# targetboard3.net
KiCad netlist of a schematic drawn in EAGLE
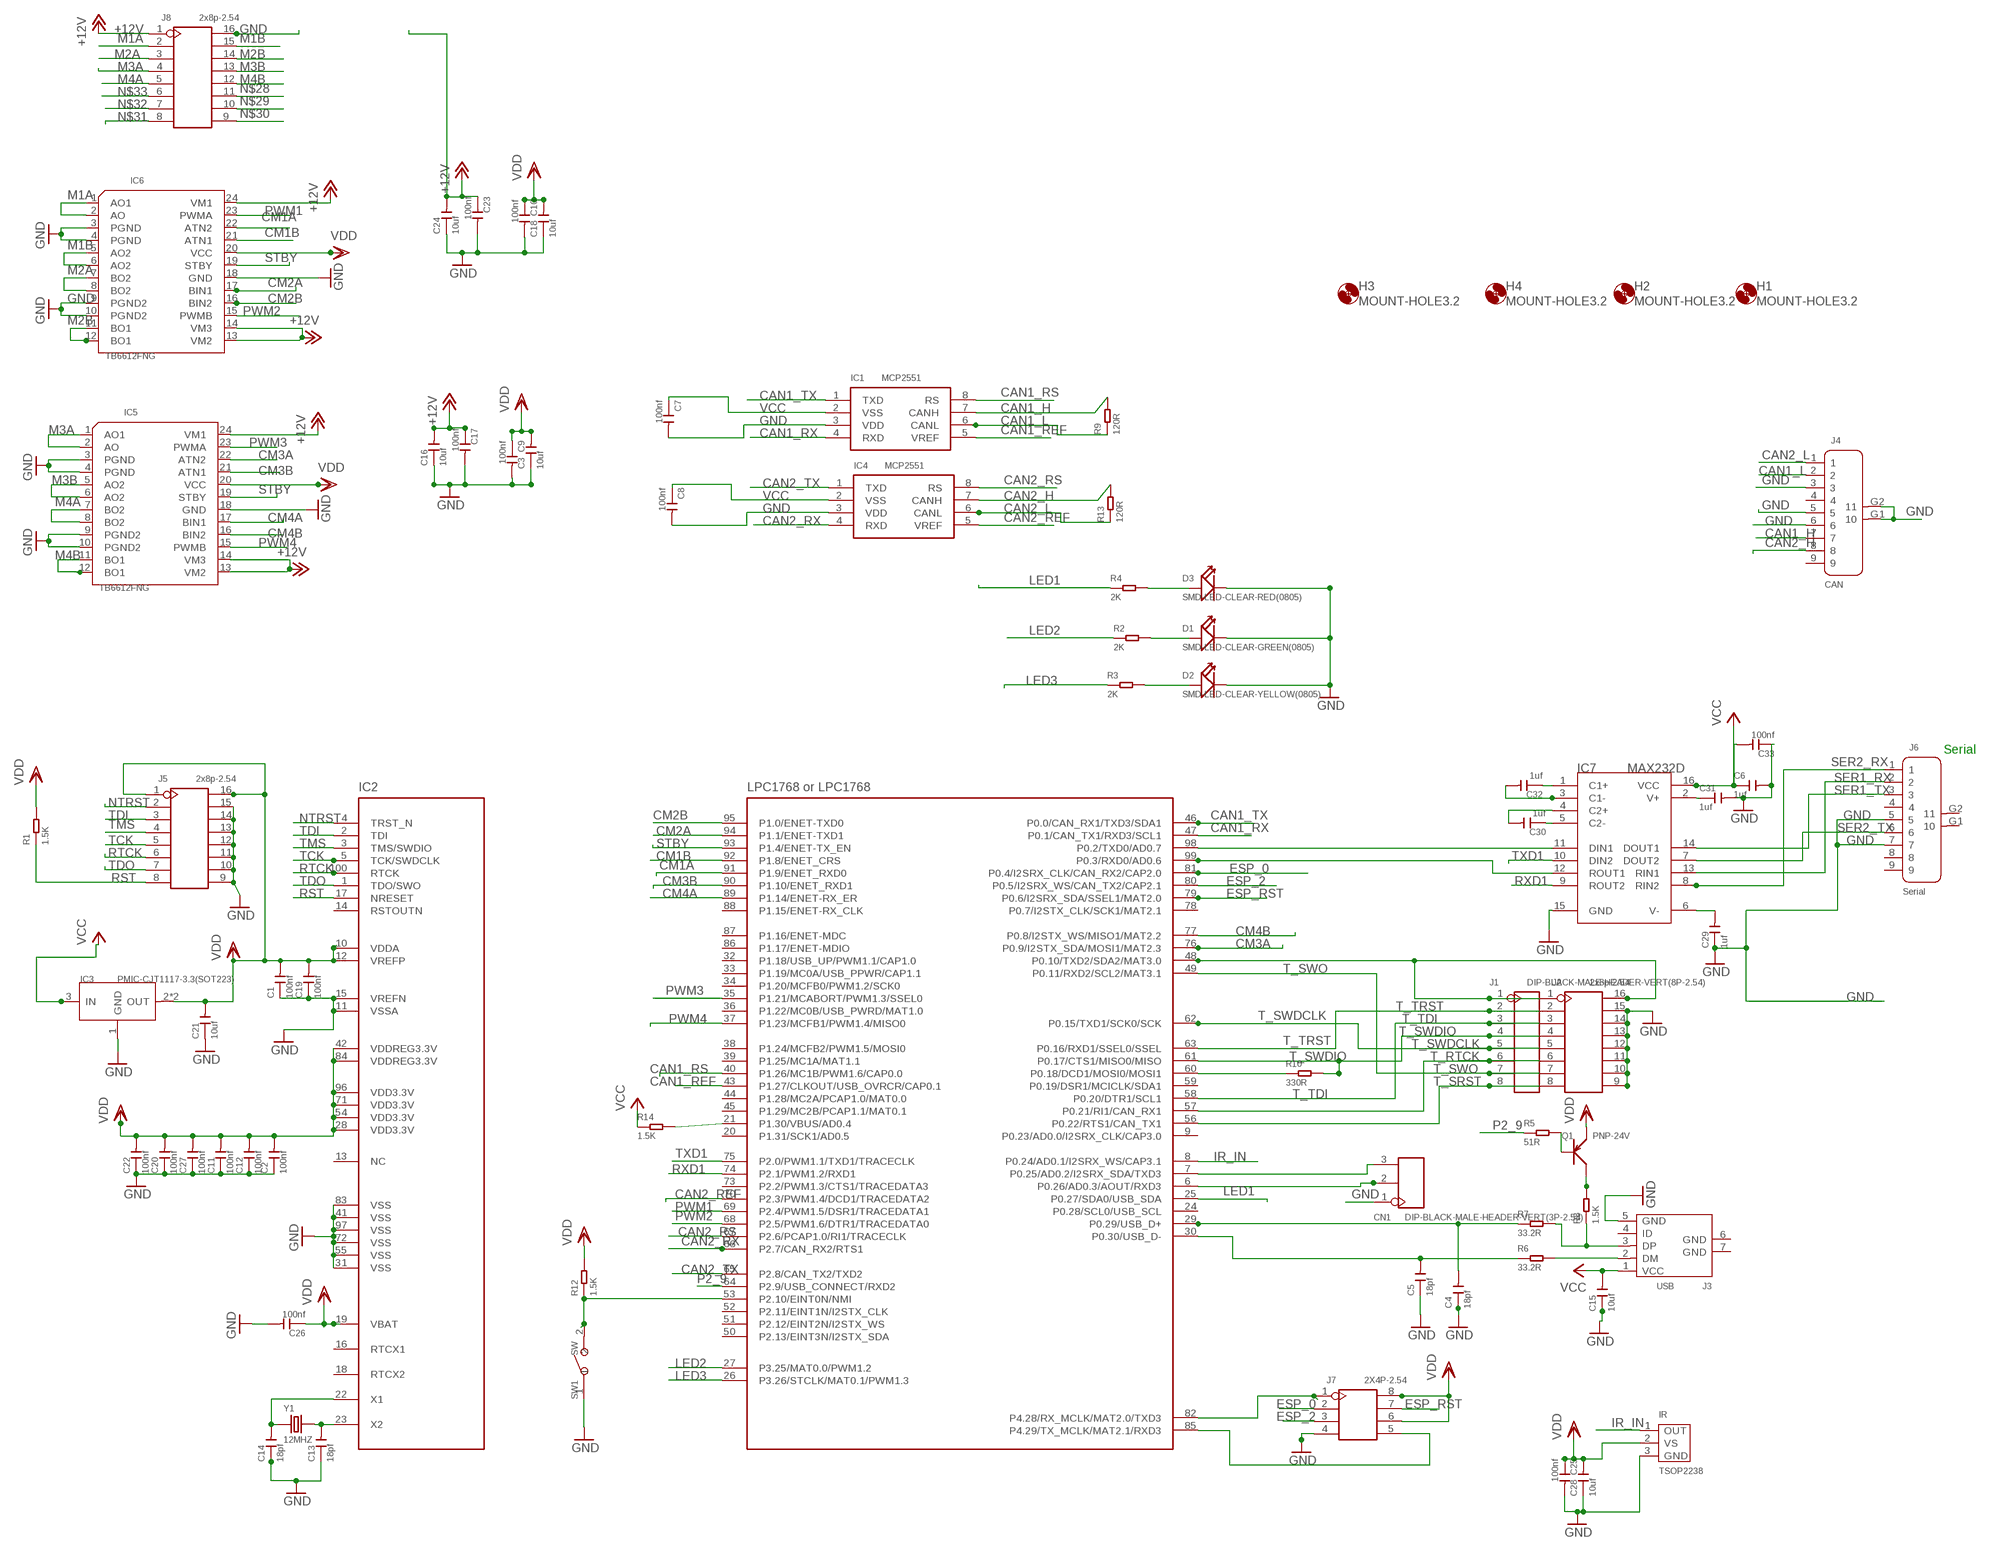
[diagram p0: schematic, sheet 1]

(export (version "E")
  (design (tool "Eeschema 10.0.6"))
  (components
    (comp (ref "C1")
      (value "100nf")
      (footprint "eagle-import:C0805")
      (fields (field (name "MPN") "CC0805KRX7R9BB104"))
      (libsource (lib "eagle-import") (part "CERAMIC-100NF-50V-10%-X7R(0805)"))
    )
    (comp (ref "C2")
      (value "100nf")
      (footprint "eagle-import:C0805")
      (fields (field (name "MPN") "CC0805KRX7R9BB104"))
      (libsource (lib "eagle-import") (part "CERAMIC-100NF-50V-10%-X7R(0805)"))
    )
    (comp (ref "C3")
      (value "10uf")
      (footprint "eagle-import:C0805")
      (fields (field (name "MPN") "CC0805KKX5R8BB106"))
      (libsource (lib "eagle-import") (part "CERAMIC-10UF-25V-10%-X5R(0805)"))
    )
    (comp (ref "C4")
      (value "18pf")
      (footprint "eagle-import:C0805")
      (libsource (lib "eagle-import") (part "CERAMIC-18PF-50V-5%-NPO(0805)"))
    )
    (comp (ref "C5")
      (value "18pf")
      (footprint "eagle-import:C0805")
      (libsource (lib "eagle-import") (part "CERAMIC-18PF-50V-5%-NPO(0805)"))
    )
    (comp (ref "C6")
      (value "1uf")
      (footprint "eagle-import:C0805")
      (fields (field (name "MPN") "CC0805KKX7R8BB105"))
      (libsource (lib "eagle-import") (part "CERAMIC-1UF-25V-10%-X7R(0805)"))
    )
    (comp (ref "C7")
      (value "100nf")
      (footprint "eagle-import:C0805")
      (fields (field (name "MPN") "CC0805KRX7R9BB104"))
      (libsource (lib "eagle-import") (part "CERAMIC-100NF-50V-10%-X7R(0805)"))
    )
    (comp (ref "C8")
      (value "100nf")
      (footprint "eagle-import:C0805")
      (fields (field (name "MPN") "CC0805KRX7R9BB104"))
      (libsource (lib "eagle-import") (part "CERAMIC-100NF-50V-10%-X7R(0805)"))
    )
    (comp (ref "C9")
      (value "100nf")
      (footprint "eagle-import:C0805")
      (fields (field (name "MPN") "CC0805KRX7R9BB104"))
      (libsource (lib "eagle-import") (part "CERAMIC-100NF-50V-10%-X7R(0805)"))
    )
    (comp (ref "C10")
      (value "100nf")
      (footprint "eagle-import:C0805")
      (fields (field (name "MPN") "CC0805KRX7R9BB104"))
      (libsource (lib "eagle-import") (part "CERAMIC-100NF-50V-10%-X7R(0805)"))
    )
    (comp (ref "C11")
      (value "100nf")
      (footprint "eagle-import:C0805")
      (fields (field (name "MPN") "CC0805KRX7R9BB104"))
      (libsource (lib "eagle-import") (part "CERAMIC-100NF-50V-10%-X7R(0805)"))
    )
    (comp (ref "C12")
      (value "100nf")
      (footprint "eagle-import:C0805")
      (fields (field (name "MPN") "CC0805KRX7R9BB104"))
      (libsource (lib "eagle-import") (part "CERAMIC-100NF-50V-10%-X7R(0805)"))
    )
    (comp (ref "C13")
      (value "18pf")
      (footprint "eagle-import:C0805")
      (libsource (lib "eagle-import") (part "CERAMIC-18PF-50V-5%-NPO(0805)"))
    )
    (comp (ref "C14")
      (value "18pf")
      (footprint "eagle-import:C0805")
      (libsource (lib "eagle-import") (part "CERAMIC-18PF-50V-5%-NPO(0805)"))
    )
    (comp (ref "C15")
      (value "10uf")
      (footprint "eagle-import:C0603")
      (fields (field (name "MPN") "CC0603KRX5R6BB106"))
      (libsource (lib "eagle-import") (part "CERAMIC-10UF-10V-10%-X5R(0603)"))
    )
    (comp (ref "C16")
      (value "10uf")
      (footprint "eagle-import:C0805")
      (fields (field (name "MPN") "CC0805KKX5R8BB106"))
      (libsource (lib "eagle-import") (part "CERAMIC-10UF-25V-10%-X5R(0805)"))
    )
    (comp (ref "C17")
      (value "100nf")
      (footprint "eagle-import:C0805")
      (fields (field (name "MPN") "CC0805KRX7R9BB104"))
      (libsource (lib "eagle-import") (part "CERAMIC-100NF-50V-10%-X7R(0805)"))
    )
    (comp (ref "C18")
      (value "10uf")
      (footprint "eagle-import:C0805")
      (fields (field (name "MPN") "CC0805KKX5R8BB106"))
      (libsource (lib "eagle-import") (part "CERAMIC-10UF-25V-10%-X5R(0805)"))
    )
    (comp (ref "C19")
      (value "100nf")
      (footprint "eagle-import:C0805")
      (fields (field (name "MPN") "CC0805KRX7R9BB104"))
      (libsource (lib "eagle-import") (part "CERAMIC-100NF-50V-10%-X7R(0805)"))
    )
    (comp (ref "C20")
      (value "100nf")
      (footprint "eagle-import:C0805")
      (fields (field (name "MPN") "CC0805KRX7R9BB104"))
      (libsource (lib "eagle-import") (part "CERAMIC-100NF-50V-10%-X7R(0805)"))
    )
    (comp (ref "C21")
      (value "10uf")
      (footprint "eagle-import:C0805")
      (fields (field (name "MPN") "CC0805KKX5R8BB106"))
      (libsource (lib "eagle-import") (part "CERAMIC-10UF-25V-10%-X5R(0805)"))
    )
    (comp (ref "C22")
      (value "100nf")
      (footprint "eagle-import:C0805")
      (fields (field (name "MPN") "CC0805KRX7R9BB104"))
      (libsource (lib "eagle-import") (part "CERAMIC-100NF-50V-10%-X7R(0805)"))
    )
    (comp (ref "C23")
      (value "100nf")
      (footprint "eagle-import:C0805")
      (fields (field (name "MPN") "CC0805KRX7R9BB104"))
      (libsource (lib "eagle-import") (part "CERAMIC-100NF-50V-10%-X7R(0805)"))
    )
    (comp (ref "C24")
      (value "10uf")
      (footprint "eagle-import:C0805")
      (fields (field (name "MPN") "CC0805KKX5R8BB106"))
      (libsource (lib "eagle-import") (part "CERAMIC-10UF-25V-10%-X5R(0805)"))
    )
    (comp (ref "C25")
      (value "100nf")
      (footprint "eagle-import:C0805")
      (fields (field (name "MPN") "CC0805KRX7R9BB104"))
      (libsource (lib "eagle-import") (part "CERAMIC-100NF-50V-10%-X7R(0805)"))
    )
    (comp (ref "C26")
      (value "100nf")
      (footprint "eagle-import:C0805")
      (fields (field (name "MPN") "CC0805KRX7R9BB104"))
      (libsource (lib "eagle-import") (part "CERAMIC-100NF-50V-10%-X7R(0805)"))
    )
    (comp (ref "C27")
      (value "100nf")
      (footprint "eagle-import:C0805")
      (fields (field (name "MPN") "CC0805KRX7R9BB104"))
      (libsource (lib "eagle-import") (part "CERAMIC-100NF-50V-10%-X7R(0805)"))
    )
    (comp (ref "C28")
      (value "10uf")
      (footprint "eagle-import:C0805")
      (fields (field (name "MPN") "CC0805KKX5R8BB106"))
      (libsource (lib "eagle-import") (part "CERAMIC-10UF-25V-10%-X5R(0805)"))
    )
    (comp (ref "C29")
      (value "1uf")
      (footprint "eagle-import:C0805")
      (fields (field (name "MPN") "CC0805KKX7R8BB105"))
      (libsource (lib "eagle-import") (part "CERAMIC-1UF-25V-10%-X7R(0805)"))
    )
    (comp (ref "C30")
      (value "1uf")
      (footprint "eagle-import:C0805")
      (fields (field (name "MPN") "CC0805KKX7R8BB105"))
      (libsource (lib "eagle-import") (part "CERAMIC-1UF-25V-10%-X7R(0805)"))
    )
    (comp (ref "C31")
      (value "1uf")
      (footprint "eagle-import:C0805")
      (fields (field (name "MPN") "CC0805KKX7R8BB105"))
      (libsource (lib "eagle-import") (part "CERAMIC-1UF-25V-10%-X7R(0805)"))
    )
    (comp (ref "C32")
      (value "1uf")
      (footprint "eagle-import:C0805")
      (fields (field (name "MPN") "CC0805KKX7R8BB105"))
      (libsource (lib "eagle-import") (part "CERAMIC-1UF-25V-10%-X7R(0805)"))
    )
    (comp (ref "C33")
      (value "100nf")
      (footprint "eagle-import:C0805")
      (fields (field (name "MPN") "CC0805KRX7R9BB104"))
      (libsource (lib "eagle-import") (part "CERAMIC-100NF-50V-10%-X7R(0805)"))
    )
    (comp (ref "CN1")
      (value "DIP-BLACK-MALE-HEADER-VERT(3P-2.54)")
      (footprint "eagle-import:H3-2.54")
      (libsource (lib "eagle-import") (part "DIP-BLACK-MALE-HEADER-VERT(3P-2.54)"))
    )
    (comp (ref "D1")
      (value "SMD-LED-CLEAR-GREEN(0805)")
      (footprint "eagle-import:LED-0805")
      (fields (field (name "MPN") "17-215SYGC/S530-E2/TR8"))
      (libsource (lib "eagle-import") (part "SMD-LED-CLEAR-GREEN(0805)"))
    )
    (comp (ref "D2")
      (value "SMD-LED-CLEAR-YELLOW(0805)")
      (footprint "eagle-import:LED-0805")
      (fields (field (name "MPN") "17-215UYC/S530-A3/TR8"))
      (libsource (lib "eagle-import") (part "SMD-LED-CLEAR-YELLOW(0805)"))
    )
    (comp (ref "D3")
      (value "SMD-LED-CLEAR-RED(0805)")
      (footprint "eagle-import:LED-0805")
      (fields (field (name "MPN") "17-215SURC/S530-A2/TR8"))
      (libsource (lib "eagle-import") (part "SMD-LED-CLEAR-RED(0805)"))
    )
    (comp (ref "H1")
      (value "MOUNT-HOLE3.2")
      (footprint "eagle-import:3,2")
      (libsource (lib "eagle-import") (part "MOUNT-HOLE3.2"))
    )
    (comp (ref "H2")
      (value "MOUNT-HOLE3.2")
      (footprint "eagle-import:3,2")
      (libsource (lib "eagle-import") (part "MOUNT-HOLE3.2"))
    )
    (comp (ref "H3")
      (value "MOUNT-HOLE3.2")
      (footprint "eagle-import:3,2")
      (libsource (lib "eagle-import") (part "MOUNT-HOLE3.2"))
    )
    (comp (ref "H4")
      (value "MOUNT-HOLE3.2")
      (footprint "eagle-import:3,2")
      (libsource (lib "eagle-import") (part "MOUNT-HOLE3.2"))
    )
    (comp (ref "IC1")
      (value "MCP2551")
      (footprint "eagle-import:SOIC8-1.27-5X4MM")
      (fields (field (name "MPN") "MCP2551-I/SN"))
      (libsource (lib "eagle-import") (part "INTERFACE-MCP2551-I/SN(SOIC8)"))
    )
    (comp (ref "IC2")
      (value "LPC1768 or LPC1768")
      (footprint "eagle-import:LQFP100-0.5-13.8X13.8MM")
      (fields (field (name "MPN") "LPC1768FBD100"))
      (libsource (lib "eagle-import") (part "MCU_LPC1768FBD100(LQFP100)"))
    )
    (comp (ref "IC3")
      (value "PMIC-CJT1117-3.3(SOT223)")
      (footprint "eagle-import:SOT-223")
      (fields (field (name "MPN") "CJT1117-3.3"))
      (libsource (lib "eagle-import") (part "PMIC-CJT1117-3.3(SOT223)"))
    )
    (comp (ref "IC4")
      (value "MCP2551")
      (footprint "eagle-import:SOIC8-1.27-5X4MM")
      (fields (field (name "MPN") "MCP2551-I/SN"))
      (libsource (lib "eagle-import") (part "INTERFACE-MCP2551-I/SN(SOIC8)"))
    )
    (comp (ref "IC5")
      (value "TB6612FNG")
      (footprint "eagle-import:SSOP24-0.65-8.9X5.3MM")
      (fields (field (name "MPN") "TB6612FNG-O/C8/EL"))
      (libsource (lib "eagle-import") (part "DRIVER-TB6612FNG-O/C8/EL(SSOP24)"))
    )
    (comp (ref "IC6")
      (value "TB6612FNG")
      (footprint "eagle-import:SSOP24-0.65-8.9X5.3MM")
      (fields (field (name "MPN") "TB6612FNG-O/C8/EL"))
      (libsource (lib "eagle-import") (part "DRIVER-TB6612FNG-O/C8/EL(SSOP24)"))
    )
    (comp (ref "IC7")
      (value "MAX232D")
      (footprint "eagle-import:SOIC16-1.27-10X3.9MM")
      (libsource (lib "eagle-import") (part "RECEIVER-MAX232D(SOIC16)"))
    )
    (comp (ref "IR")
      (value "TSOP2238")
      (footprint "eagle-import:SNR3-2.54-6.95X6.0X5.6MM")
      (libsource (lib "eagle-import") (part "OPTICAL-TSOP2238"))
    )
    (comp (ref "J1")
      (value "DIP-BLACK-MALE-HEADER-VERT(8P-2.54)")
      (footprint "eagle-import:H8-2.54")
      (fields (field (name "MPN") "P125-1108A1BS116A1"))
      (libsource (lib "eagle-import") (part "DIP-BLACK-MALE-HEADER-VERT(8P-2.54)"))
    )
    (comp (ref "J2")
      (value "2x8p-2.54")
      (footprint "eagle-import:H2X8-2.54")
      (fields (field (name "MPN") "P125-1216A0AS116A1"))
      (libsource (lib "eagle-import") (part "DIP-BLACK-MALE-HEADER-VERT(2X8P-2.54)"))
    )
    (comp (ref "J3")
      (value "USB")
      (footprint "eagle-import:MICRO-USB5+2P-SMD-0.65")
      (fields (field (name "MPN") "ST-USB-001L"))
      (libsource (lib "eagle-import") (part "MICRO-USB-SMD-TYPE-AB-R/A(ST-USB-001L)"))
    )
    (comp (ref "J4")
      (value "CAN")
      (footprint "eagle-import:DSUB9+2P-2.77-90D-MALE")
      (libsource (lib "eagle-import") (part "DIP-MALE-DB9-CONNECTOR"))
    )
    (comp (ref "J5")
      (value "2x8p-2.54")
      (footprint "eagle-import:H2X8-2.54")
      (fields (field (name "MPN") "P125-1216A0AS116A1"))
      (libsource (lib "eagle-import") (part "DIP-BLACK-MALE-HEADER-VERT(2X8P-2.54)"))
    )
    (comp (ref "J6")
      (value "Serial")
      (footprint "eagle-import:DSUB9+2P-2.77-90D-MALE")
      (libsource (lib "eagle-import") (part "DIP-MALE-DB9-CONNECTOR"))
    )
    (comp (ref "J7")
      (value "2X4P-2.54")
      (footprint "eagle-import:H2X4-2.54")
      (libsource (lib "eagle-import") (part "DIP-BLACK-FEMALE-HEADER(2X4P-2.54)"))
    )
    (comp (ref "J8")
      (value "2x8p-2.54")
      (footprint "eagle-import:H2X8-2.54")
      (fields (field (name "MPN") "P125-1216A0AS116A1"))
      (libsource (lib "eagle-import") (part "DIP-BLACK-MALE-HEADER-VERT(2X8P-2.54)"))
    )
    (comp (ref "Q1")
      (value "PNP-24V")
      (footprint "eagle-import:SOT-23")
      (fields (field (name "MPN") "S8550"))
      (libsource (lib "eagle-import") (part "SMD-TRANSISTORS-PNP-25V-500MA(SOT-23)"))
    )
    (comp (ref "R1")
      (value "1.5K")
      (footprint "eagle-import:R0805")
      (fields (field (name "MPN") "RC0805FR-071K5L"))
      (libsource (lib "eagle-import") (part "SMD-RES-1.5K-1%-1/8W(0805)"))
    )
    (comp (ref "R2")
      (value "2K")
      (footprint "eagle-import:R0805")
      (fields (field (name "MPN") "RC0805JR-072KL"))
      (libsource (lib "eagle-import") (part "SMD-RES-2K-5%-1/8W(0805)"))
    )
    (comp (ref "R3")
      (value "2K")
      (footprint "eagle-import:R0805")
      (fields (field (name "MPN") "RC0805JR-072KL"))
      (libsource (lib "eagle-import") (part "SMD-RES-2K-5%-1/8W(0805)"))
    )
    (comp (ref "R4")
      (value "2K")
      (footprint "eagle-import:R0805")
      (fields (field (name "MPN") "RC0805JR-072KL"))
      (libsource (lib "eagle-import") (part "SMD-RES-2K-5%-1/8W(0805)"))
    )
    (comp (ref "R5")
      (value "51R")
      (footprint "eagle-import:R0603")
      (fields (field (name "MPN") "RC0603FR-0751RL"))
      (libsource (lib "eagle-import") (part "SMD-RES-51R-1%-1/10W(0603)"))
    )
    (comp (ref "R6")
      (value "33.2R")
      (footprint "eagle-import:R0603")
      (fields (field (name "MPN") "RC0603FR-0733R2L"))
      (libsource (lib "eagle-import") (part "SMD-RES-33.2R-1%-1/10W(0603)"))
    )
    (comp (ref "R7")
      (value "33.2R")
      (footprint "eagle-import:R0603")
      (fields (field (name "MPN") "RC0603FR-0733R2L"))
      (libsource (lib "eagle-import") (part "SMD-RES-33.2R-1%-1/10W(0603)"))
    )
    (comp (ref "R8")
      (value "1.5K")
      (footprint "eagle-import:R0805")
      (fields (field (name "MPN") "RC0805FR-071K5L"))
      (libsource (lib "eagle-import") (part "SMD-RES-1.5K-1%-1/8W(0805)"))
    )
    (comp (ref "R9")
      (value "120R")
      (footprint "eagle-import:R0805")
      (fields (field (name "MPN") "RC0805JR-07120RL"))
      (libsource (lib "eagle-import") (part "SMD-RES-120R-5%-1/8W(0805)"))
    )
    (comp (ref "R10")
      (value "330R")
      (footprint "eagle-import:R0603")
      (fields (field (name "MPN") "RC0603FR-07330RL"))
      (libsource (lib "eagle-import") (part "SMD-RES-330R-1%-1/10W(0603)"))
    )
    (comp (ref "R12")
      (value "1.5K")
      (footprint "eagle-import:R0805")
      (fields (field (name "MPN") "RC0805FR-071K5L"))
      (libsource (lib "eagle-import") (part "SMD-RES-1.5K-1%-1/8W(0805)"))
    )
    (comp (ref "R13")
      (value "120R")
      (footprint "eagle-import:R0805")
      (fields (field (name "MPN") "RC0805JR-07120RL"))
      (libsource (lib "eagle-import") (part "SMD-RES-120R-5%-1/8W(0805)"))
    )
    (comp (ref "R14")
      (value "1.5K")
      (footprint "eagle-import:R0805")
      (fields (field (name "MPN") "RC0805FR-071K5L"))
      (libsource (lib "eagle-import") (part "SMD-RES-1.5K-1%-1/8W(0805)"))
    )
    (comp (ref "SW1")
      (value "SW")
      (footprint "eagle-import:SW2-2.6-3.0X2.5X1.2+0.4MM")
      (libsource (lib "eagle-import") (part "SMD-BUTTON(2P-3.0X2.5X1.2+0.4MM)-B3U-1000P-2P-SMD"))
    )
    (comp (ref "Y1")
      (value "12MHZ")
      (footprint "eagle-import:X2-SMD-5.0X3.2X1.3MM")
      (fields (field (name "MPN") "5032/2P"))
      (libsource (lib "eagle-import") (part "SMD-CRYSTAL-12MHZ-20PF-20PPM-40R(2P-5.0X3.2MM)"))
    )
  )
  (nets
    (net (code "1") (name "+12V") (class "Default")
      (node (ref "C16") (pin "2") (pinfunction "2_2") (pintype "passive"))
      (node (ref "C17") (pin "1") (pinfunction "1_1") (pintype "passive"))
      (node (ref "C23") (pin "1") (pinfunction "1_1") (pintype "passive"))
      (node (ref "C24") (pin "2") (pinfunction "2_2") (pintype "passive"))
      (node (ref "IC5") (pin "13") (pinfunction "VM2_13") (pintype "bidirectional"))
      (node (ref "IC5") (pin "14") (pinfunction "VM3_14") (pintype "bidirectional"))
      (node (ref "IC5") (pin "24") (pinfunction "VM1_24") (pintype "bidirectional"))
      (node (ref "IC6") (pin "13") (pinfunction "VM2_13") (pintype "bidirectional"))
      (node (ref "IC6") (pin "14") (pinfunction "VM3_14") (pintype "bidirectional"))
      (node (ref "IC6") (pin "24") (pinfunction "VM1_24") (pintype "bidirectional"))
      (node (ref "J8") (pin "1") (pinfunction "1_1") (pintype "bidirectional"))
    )
    (net (code "2") (name "/CAN1_H") (class "Default")
      (node (ref "IC1") (pin "7") (pinfunction "CANH_7") (pintype "bidirectional"))
      (node (ref "J4") (pin "7") (pinfunction "7_7") (pintype "bidirectional"))
      (node (ref "R9") (pin "2") (pinfunction "2_2") (pintype "passive"))
    )
    (net (code "3") (name "/CAN1_L") (class "Default")
      (node (ref "IC1") (pin "6") (pinfunction "CANL_6") (pintype "bidirectional"))
      (node (ref "J4") (pin "2") (pinfunction "2_2") (pintype "bidirectional"))
      (node (ref "R9") (pin "1") (pinfunction "1_1") (pintype "passive"))
    )
    (net (code "4") (name "/CAN1_REF") (class "Default")
      (node (ref "IC1") (pin "5") (pinfunction "VREF_5") (pintype "bidirectional"))
      (node (ref "IC2") (pin "43") (pinfunction "P1.27/CLKOUT/USB_OVRCR/CAP0.1_43") (pintype "bidirectional"))
    )
    (net (code "5") (name "/CAN1_RS") (class "Default")
      (node (ref "IC1") (pin "8") (pinfunction "RS_8") (pintype "bidirectional"))
      (node (ref "IC2") (pin "40") (pinfunction "P1.26/MC1B/PWM1.6/CAP0.0_40") (pintype "bidirectional"))
    )
    (net (code "6") (name "/CAN1_RX") (class "Default")
      (node (ref "IC1") (pin "4") (pinfunction "RXD_4") (pintype "bidirectional"))
      (node (ref "IC2") (pin "47") (pinfunction "P0.1/CAN_TX1/RXD3/SCL1_47") (pintype "bidirectional"))
    )
    (net (code "7") (name "/CAN1_TX") (class "Default")
      (node (ref "IC1") (pin "1") (pinfunction "TXD_1") (pintype "bidirectional"))
      (node (ref "IC2") (pin "46") (pinfunction "P0.0/CAN_RX1/TXD3/SDA1_46") (pintype "bidirectional"))
    )
    (net (code "8") (name "/CAN2_H") (class "Default")
      (node (ref "IC4") (pin "7") (pinfunction "CANH_7") (pintype "bidirectional"))
      (node (ref "J4") (pin "8") (pinfunction "8_8") (pintype "bidirectional"))
      (node (ref "R13") (pin "2") (pinfunction "2_2") (pintype "passive"))
    )
    (net (code "9") (name "/CAN2_L") (class "Default")
      (node (ref "IC4") (pin "6") (pinfunction "CANL_6") (pintype "bidirectional"))
      (node (ref "J4") (pin "1") (pinfunction "1_1") (pintype "bidirectional"))
      (node (ref "R13") (pin "1") (pinfunction "1_1") (pintype "passive"))
    )
    (net (code "10") (name "/CAN2_REF") (class "Default")
      (node (ref "IC2") (pin "70") (pinfunction "P2.3/PWM1.4/DCD1/TRACEDATA2_70") (pintype "bidirectional"))
      (node (ref "IC4") (pin "5") (pinfunction "VREF_5") (pintype "bidirectional"))
    )
    (net (code "11") (name "/CAN2_RS") (class "Default")
      (node (ref "IC2") (pin "67") (pinfunction "P2.6/PCAP1.0/RI1/TRACECLK_67") (pintype "bidirectional"))
      (node (ref "IC4") (pin "8") (pinfunction "RS_8") (pintype "bidirectional"))
    )
    (net (code "12") (name "/CAN2_RX") (class "Default")
      (node (ref "IC2") (pin "66") (pinfunction "P2.7/CAN_RX2/RTS1_66") (pintype "bidirectional"))
      (node (ref "IC4") (pin "4") (pinfunction "RXD_4") (pintype "bidirectional"))
    )
    (net (code "13") (name "/CAN2_TX") (class "Default")
      (node (ref "IC2") (pin "65") (pinfunction "P2.8/CAN_TX2/TXD2_65") (pintype "bidirectional"))
      (node (ref "IC4") (pin "1") (pinfunction "TXD_1") (pintype "bidirectional"))
    )
    (net (code "14") (name "/CM1A") (class "Default")
      (node (ref "IC2") (pin "91") (pinfunction "P1.9/ENET_RXD0_91") (pintype "bidirectional"))
      (node (ref "IC6") (pin "22") (pinfunction "ATN2_22") (pintype "bidirectional"))
    )
    (net (code "15") (name "/CM1B") (class "Default")
      (node (ref "IC2") (pin "92") (pinfunction "P1.8/ENET_CRS_92") (pintype "bidirectional"))
      (node (ref "IC6") (pin "21") (pinfunction "ATN1_21") (pintype "bidirectional"))
    )
    (net (code "16") (name "/CM2A") (class "Default")
      (node (ref "IC2") (pin "94") (pinfunction "P1.1/ENET-TXD1_94") (pintype "bidirectional"))
      (node (ref "IC6") (pin "17") (pinfunction "BIN1_17") (pintype "bidirectional"))
    )
    (net (code "17") (name "/CM2B") (class "Default")
      (node (ref "IC2") (pin "95") (pinfunction "P1.0/ENET-TXD0_95") (pintype "bidirectional"))
      (node (ref "IC6") (pin "16") (pinfunction "BIN2_16") (pintype "bidirectional"))
    )
    (net (code "18") (name "/CM3A") (class "Default")
      (node (ref "IC2") (pin "76") (pinfunction "P0.9/I2STX_SDA/MOSI1/MAT2.3_76") (pintype "bidirectional"))
      (node (ref "IC5") (pin "22") (pinfunction "ATN2_22") (pintype "bidirectional"))
    )
    (net (code "19") (name "/CM3B") (class "Default")
      (node (ref "IC2") (pin "90") (pinfunction "P1.10/ENET_RXD1_90") (pintype "bidirectional"))
      (node (ref "IC5") (pin "21") (pinfunction "ATN1_21") (pintype "bidirectional"))
    )
    (net (code "20") (name "/CM4A") (class "Default")
      (node (ref "IC2") (pin "89") (pinfunction "P1.14/ENET-RX_ER_89") (pintype "bidirectional"))
      (node (ref "IC5") (pin "17") (pinfunction "BIN1_17") (pintype "bidirectional"))
    )
    (net (code "21") (name "/CM4B") (class "Default")
      (node (ref "IC2") (pin "77") (pinfunction "P0.8/I2STX_WS/MISO1/MAT2.2_77") (pintype "bidirectional"))
      (node (ref "IC5") (pin "16") (pinfunction "BIN2_16") (pintype "bidirectional"))
    )
    (net (code "22") (name "/ESP_0") (class "Default")
      (node (ref "IC2") (pin "81") (pinfunction "P0.4/I2SRX_CLK/CAN_RX2/CAP2.0_81") (pintype "bidirectional"))
      (node (ref "J7") (pin "2") (pinfunction "2_2") (pintype "bidirectional"))
    )
    (net (code "23") (name "/ESP_2") (class "Default")
      (node (ref "IC2") (pin "80") (pinfunction "P0.5/I2SRX_WS/CAN_TX2/CAP2.1_80") (pintype "bidirectional"))
      (node (ref "J7") (pin "3") (pinfunction "3_3") (pintype "bidirectional"))
    )
    (net (code "24") (name "/ESP_RST") (class "Default")
      (node (ref "IC2") (pin "79") (pinfunction "P0.6/I2SRX_SDA/SSEL1/MAT2.0_79") (pintype "bidirectional"))
      (node (ref "J7") (pin "7") (pinfunction "7_7") (pintype "bidirectional"))
    )
    (net (code "25") (name "/IR_IN") (class "Default")
      (node (ref "IC2") (pin "8") (pinfunction "P0.24/AD0.1/I2SRX_WS/CAP3.1_8") (pintype "bidirectional"))
      (node (ref "IR") (pin "1") (pinfunction "OUT_1") (pintype "bidirectional"))
    )
    (net (code "26") (name "/LED1") (class "Default")
      (node (ref "IC2") (pin "25") (pinfunction "P0.27/SDA0/USB_SDA_25") (pintype "bidirectional"))
      (node (ref "R4") (pin "1") (pinfunction "1_1") (pintype "passive"))
    )
    (net (code "27") (name "/LED2") (class "Default")
      (node (ref "IC2") (pin "27") (pinfunction "P3.25/MAT0.0/PWM1.2_27") (pintype "bidirectional"))
      (node (ref "R2") (pin "1") (pinfunction "1_1") (pintype "passive"))
    )
    (net (code "28") (name "/LED3") (class "Default")
      (node (ref "IC2") (pin "26") (pinfunction "P3.26/STCLK/MAT0.1/PWM1.3_26") (pintype "bidirectional"))
      (node (ref "R3") (pin "1") (pinfunction "1_1") (pintype "passive"))
    )
    (net (code "29") (name "/M1A") (class "Default")
      (node (ref "IC6") (pin "1") (pinfunction "AO1_1") (pintype "bidirectional"))
      (node (ref "IC6") (pin "2") (pinfunction "AO_2") (pintype "bidirectional"))
      (node (ref "J8") (pin "2") (pinfunction "2_2") (pintype "bidirectional"))
    )
    (net (code "30") (name "/M1B") (class "Default")
      (node (ref "IC6") (pin "5") (pinfunction "AO2_5") (pintype "bidirectional"))
      (node (ref "IC6") (pin "6") (pinfunction "AO2_6") (pintype "bidirectional"))
      (node (ref "J8") (pin "15") (pinfunction "15_15") (pintype "bidirectional"))
    )
    (net (code "31") (name "/M2A") (class "Default")
      (node (ref "IC6") (pin "7") (pinfunction "BO2_7") (pintype "bidirectional"))
      (node (ref "IC6") (pin "8") (pinfunction "BO2_8") (pintype "bidirectional"))
      (node (ref "J8") (pin "3") (pinfunction "3_3") (pintype "bidirectional"))
    )
    (net (code "32") (name "/M2B") (class "Default")
      (node (ref "IC6") (pin "11") (pinfunction "BO1_11") (pintype "bidirectional"))
      (node (ref "IC6") (pin "12") (pinfunction "BO1_12") (pintype "bidirectional"))
      (node (ref "J8") (pin "14") (pinfunction "14_14") (pintype "bidirectional"))
    )
    (net (code "33") (name "/M3A") (class "Default")
      (node (ref "IC5") (pin "1") (pinfunction "AO1_1") (pintype "bidirectional"))
      (node (ref "IC5") (pin "2") (pinfunction "AO_2") (pintype "bidirectional"))
      (node (ref "J8") (pin "4") (pinfunction "4_4") (pintype "bidirectional"))
    )
    (net (code "34") (name "/M3B") (class "Default")
      (node (ref "IC5") (pin "5") (pinfunction "AO2_5") (pintype "bidirectional"))
      (node (ref "IC5") (pin "6") (pinfunction "AO2_6") (pintype "bidirectional"))
      (node (ref "J8") (pin "13") (pinfunction "13_13") (pintype "bidirectional"))
    )
    (net (code "35") (name "/M4A") (class "Default")
      (node (ref "IC5") (pin "7") (pinfunction "BO2_7") (pintype "bidirectional"))
      (node (ref "IC5") (pin "8") (pinfunction "BO2_8") (pintype "bidirectional"))
      (node (ref "J8") (pin "5") (pinfunction "5_5") (pintype "bidirectional"))
    )
    (net (code "36") (name "/M4B") (class "Default")
      (node (ref "IC5") (pin "11") (pinfunction "BO1_11") (pintype "bidirectional"))
      (node (ref "IC5") (pin "12") (pinfunction "BO1_12") (pintype "bidirectional"))
      (node (ref "J8") (pin "12") (pinfunction "12_12") (pintype "bidirectional"))
    )
    (net (code "37") (name "/N$28") (class "Default")
      (node (ref "J8") (pin "11") (pinfunction "11_11") (pintype "bidirectional"))
    )
    (net (code "38") (name "/N$29") (class "Default")
      (node (ref "J8") (pin "10") (pinfunction "10_10") (pintype "bidirectional"))
    )
    (net (code "39") (name "/N$30") (class "Default")
      (node (ref "J8") (pin "9") (pinfunction "9_9") (pintype "bidirectional"))
    )
    (net (code "40") (name "/N$31") (class "Default")
      (node (ref "J8") (pin "8") (pinfunction "8_8") (pintype "bidirectional"))
    )
    (net (code "41") (name "/N$32") (class "Default")
      (node (ref "J8") (pin "7") (pinfunction "7_7") (pintype "bidirectional"))
    )
    (net (code "42") (name "/N$33") (class "Default")
      (node (ref "J8") (pin "6") (pinfunction "6_6") (pintype "bidirectional"))
    )
    (net (code "43") (name "/NTRST") (class "Default")
      (node (ref "IC2") (pin "4") (pinfunction "TRST_N_4") (pintype "bidirectional"))
      (node (ref "J5") (pin "2") (pinfunction "2_2") (pintype "bidirectional"))
    )
    (net (code "44") (name "/P2_9") (class "Default")
      (node (ref "IC2") (pin "64") (pinfunction "P2.9/USB_CONNECT/RXD2_64") (pintype "bidirectional"))
      (node (ref "R5") (pin "1") (pinfunction "1_1") (pintype "passive"))
    )
    (net (code "45") (name "/PWM1") (class "Default")
      (node (ref "IC2") (pin "69") (pinfunction "P2.4/PWM1.5/DSR1/TRACEDATA1_69") (pintype "bidirectional"))
      (node (ref "IC6") (pin "23") (pinfunction "PWMA_23") (pintype "bidirectional"))
    )
    (net (code "46") (name "/PWM2") (class "Default")
      (node (ref "IC2") (pin "68") (pinfunction "P2.5/PWM1.6/DTR1/TRACEDATA0_68") (pintype "bidirectional"))
      (node (ref "IC6") (pin "15") (pinfunction "PWMB_15") (pintype "bidirectional"))
    )
    (net (code "47") (name "/PWM3") (class "Default")
      (node (ref "IC2") (pin "35") (pinfunction "P1.21/MCABORT/PWM1.3/SSEL0_35") (pintype "bidirectional"))
      (node (ref "IC5") (pin "23") (pinfunction "PWMA_23") (pintype "bidirectional"))
    )
    (net (code "48") (name "/PWM4") (class "Default")
      (node (ref "IC2") (pin "37") (pinfunction "P1.23/MCFB1/PWM1.4/MISO0_37") (pintype "bidirectional"))
      (node (ref "IC5") (pin "15") (pinfunction "PWMB_15") (pintype "bidirectional"))
    )
    (net (code "49") (name "/RST") (class "Default")
      (node (ref "IC2") (pin "17") (pinfunction "NRESET_17") (pintype "bidirectional"))
      (node (ref "J5") (pin "8") (pinfunction "8_8") (pintype "bidirectional"))
      (node (ref "R1") (pin "1") (pinfunction "1_1") (pintype "passive"))
    )
    (net (code "50") (name "/RTCK") (class "Default")
      (node (ref "IC2") (pin "100") (pinfunction "RTCK_100") (pintype "bidirectional"))
      (node (ref "J5") (pin "6") (pinfunction "6_6") (pintype "bidirectional"))
    )
    (net (code "51") (name "/RXD1") (class "Default")
      (node (ref "IC2") (pin "74") (pinfunction "P2.1/PWM1.2/RXD1_74") (pintype "bidirectional"))
      (node (ref "IC7") (pin "9") (pinfunction "ROUT2_9") (pintype "bidirectional"))
    )
    (net (code "52") (name "/SER1_RX") (class "Default")
      (node (ref "IC7") (pin "13") (pinfunction "RIN1_13") (pintype "bidirectional"))
      (node (ref "J6") (pin "2") (pinfunction "2_2") (pintype "bidirectional"))
    )
    (net (code "53") (name "/SER1_TX") (class "Default")
      (node (ref "IC7") (pin "14") (pinfunction "DOUT1_14") (pintype "bidirectional"))
      (node (ref "J6") (pin "3") (pinfunction "3_3") (pintype "bidirectional"))
    )
    (net (code "54") (name "/SER2_RX") (class "Default")
      (node (ref "IC7") (pin "8") (pinfunction "RIN2_8") (pintype "bidirectional"))
      (node (ref "J6") (pin "1") (pinfunction "1_1") (pintype "bidirectional"))
    )
    (net (code "55") (name "/SER2_TX") (class "Default")
      (node (ref "IC7") (pin "7") (pinfunction "DOUT2_7") (pintype "bidirectional"))
      (node (ref "J6") (pin "6") (pinfunction "6_6") (pintype "bidirectional"))
    )
    (net (code "56") (name "/STBY") (class "Default")
      (node (ref "IC2") (pin "93") (pinfunction "P1.4/ENET-TX_EN_93") (pintype "bidirectional"))
      (node (ref "IC5") (pin "19") (pinfunction "STBY_19") (pintype "bidirectional"))
      (node (ref "IC6") (pin "19") (pinfunction "STBY_19") (pintype "bidirectional"))
    )
    (net (code "57") (name "/TCK") (class "Default")
      (node (ref "IC2") (pin "5") (pinfunction "TCK/SWDCLK_5") (pintype "bidirectional"))
      (node (ref "J5") (pin "5") (pinfunction "5_5") (pintype "bidirectional"))
    )
    (net (code "58") (name "/TDI") (class "Default")
      (node (ref "IC2") (pin "2") (pinfunction "TDI_2") (pintype "bidirectional"))
      (node (ref "J5") (pin "3") (pinfunction "3_3") (pintype "bidirectional"))
    )
    (net (code "59") (name "/TDO") (class "Default")
      (node (ref "IC2") (pin "1") (pinfunction "TDO/SWO_1") (pintype "bidirectional"))
      (node (ref "J5") (pin "7") (pinfunction "7_7") (pintype "bidirectional"))
    )
    (net (code "60") (name "/TMS") (class "Default")
      (node (ref "IC2") (pin "3") (pinfunction "TMS/SWDIO_3") (pintype "bidirectional"))
      (node (ref "J5") (pin "4") (pinfunction "4_4") (pintype "bidirectional"))
    )
    (net (code "61") (name "/TXD1") (class "Default")
      (node (ref "IC2") (pin "75") (pinfunction "P2.0/PWM1.1/TXD1/TRACECLK_75") (pintype "bidirectional"))
      (node (ref "IC7") (pin "10") (pinfunction "DIN2_10") (pintype "bidirectional"))
    )
    (net (code "62") (name "/T_RTCK") (class "Default")
      (node (ref "IC2") (pin "57") (pinfunction "P0.21/RI1/CAN_RX1_57") (pintype "bidirectional"))
      (node (ref "J1") (pin "6") (pinfunction "6_6") (pintype "bidirectional"))
      (node (ref "J2") (pin "6") (pinfunction "6_6") (pintype "bidirectional"))
    )
    (net (code "63") (name "/T_SRST") (class "Default")
      (node (ref "IC2") (pin "56") (pinfunction "P0.22/RTS1/CAN_TX1_56") (pintype "bidirectional"))
      (node (ref "J1") (pin "8") (pinfunction "8_8") (pintype "bidirectional"))
      (node (ref "J2") (pin "8") (pinfunction "8_8") (pintype "bidirectional"))
    )
    (net (code "64") (name "/T_SWDCLK") (class "Default")
      (node (ref "IC2") (pin "62") (pinfunction "P0.15/TXD1/SCK0/SCK_62") (pintype "bidirectional"))
      (node (ref "J1") (pin "5") (pinfunction "5_5") (pintype "bidirectional"))
      (node (ref "J2") (pin "5") (pinfunction "5_5") (pintype "bidirectional"))
    )
    (net (code "65") (name "/T_SWDIO") (class "Default")
      (node (ref "IC2") (pin "61") (pinfunction "P0.17/CTS1/MISO0/MISO_61") (pintype "bidirectional"))
      (node (ref "J1") (pin "4") (pinfunction "4_4") (pintype "bidirectional"))
      (node (ref "J2") (pin "4") (pinfunction "4_4") (pintype "bidirectional"))
      (node (ref "R10") (pin "2") (pinfunction "2_2") (pintype "passive"))
    )
    (net (code "66") (name "/T_SWO") (class "Default")
      (node (ref "IC2") (pin "49") (pinfunction "P0.11/RXD2/SCL2/MAT3.1_49") (pintype "bidirectional"))
      (node (ref "J1") (pin "7") (pinfunction "7_7") (pintype "bidirectional"))
      (node (ref "J2") (pin "7") (pinfunction "7_7") (pintype "bidirectional"))
    )
    (net (code "67") (name "/T_TDI") (class "Default")
      (node (ref "IC2") (pin "58") (pinfunction "P0.20/DTR1/SCL1_58") (pintype "bidirectional"))
      (node (ref "J1") (pin "3") (pinfunction "3_3") (pintype "bidirectional"))
      (node (ref "J2") (pin "3") (pinfunction "3_3") (pintype "bidirectional"))
    )
    (net (code "68") (name "/T_TRST") (class "Default")
      (node (ref "IC2") (pin "63") (pinfunction "P0.16/RXD1/SSEL0/SSEL_63") (pintype "bidirectional"))
      (node (ref "J1") (pin "2") (pinfunction "2_2") (pintype "bidirectional"))
      (node (ref "J2") (pin "2") (pinfunction "2_2") (pintype "bidirectional"))
    )
    (net (code "69") (name "GND") (class "Default")
      (node (ref "C1") (pin "1") (pinfunction "1_1") (pintype "passive"))
      (node (ref "C10") (pin "2") (pinfunction "2_2") (pintype "passive"))
      (node (ref "C11") (pin "1") (pinfunction "1_1") (pintype "passive"))
      (node (ref "C12") (pin "1") (pinfunction "1_1") (pintype "passive"))
      (node (ref "C13") (pin "1") (pinfunction "1_1") (pintype "passive"))
      (node (ref "C14") (pin "1") (pinfunction "1_1") (pintype "passive"))
      (node (ref "C15") (pin "1") (pinfunction "1_1") (pintype "passive"))
      (node (ref "C16") (pin "1") (pinfunction "1_1") (pintype "passive"))
      (node (ref "C17") (pin "2") (pinfunction "2_2") (pintype "passive"))
      (node (ref "C18") (pin "1") (pinfunction "1_1") (pintype "passive"))
      (node (ref "C19") (pin "1") (pinfunction "1_1") (pintype "passive"))
      (node (ref "C2") (pin "1") (pinfunction "1_1") (pintype "passive"))
      (node (ref "C20") (pin "1") (pinfunction "1_1") (pintype "passive"))
      (node (ref "C21") (pin "1") (pinfunction "1_1") (pintype "passive"))
      (node (ref "C22") (pin "1") (pinfunction "1_1") (pintype "passive"))
      (node (ref "C23") (pin "2") (pinfunction "2_2") (pintype "passive"))
      (node (ref "C24") (pin "1") (pinfunction "1_1") (pintype "passive"))
      (node (ref "C25") (pin "2") (pinfunction "2_2") (pintype "passive"))
      (node (ref "C26") (pin "2") (pinfunction "2_2") (pintype "passive"))
      (node (ref "C27") (pin "1") (pinfunction "1_1") (pintype "passive"))
      (node (ref "C28") (pin "1") (pinfunction "1_1") (pintype "passive"))
      (node (ref "C29") (pin "1") (pinfunction "1_1") (pintype "passive"))
      (node (ref "C3") (pin "1") (pinfunction "1_1") (pintype "passive"))
      (node (ref "C31") (pin "2") (pinfunction "2_2") (pintype "passive"))
      (node (ref "C33") (pin "1") (pinfunction "1_1") (pintype "passive"))
      (node (ref "C4") (pin "1") (pinfunction "1_1") (pintype "passive"))
      (node (ref "C5") (pin "1") (pinfunction "1_1") (pintype "passive"))
      (node (ref "C6") (pin "2") (pinfunction "2_2") (pintype "passive"))
      (node (ref "C7") (pin "2") (pinfunction "2_2") (pintype "passive"))
      (node (ref "C8") (pin "2") (pinfunction "2_2") (pintype "passive"))
      (node (ref "C9") (pin "2") (pinfunction "2_2") (pintype "passive"))
      (node (ref "CN1") (pin "1") (pinfunction "P$1_1") (pintype "bidirectional"))
      (node (ref "D1") (pin "-") (pinfunction "-_-") (pintype "passive"))
      (node (ref "D2") (pin "-") (pinfunction "-_-") (pintype "passive"))
      (node (ref "D3") (pin "-") (pinfunction "-_-") (pintype "passive"))
      (node (ref "IC1") (pin "3") (pinfunction "VDD_3") (pintype "bidirectional"))
      (node (ref "IC2") (pin "11") (pinfunction "VSSA_11") (pintype "bidirectional"))
      (node (ref "IC2") (pin "15") (pinfunction "VREFN_15") (pintype "bidirectional"))
      (node (ref "IC2") (pin "31") (pinfunction "VSS_31") (pintype "bidirectional"))
      (node (ref "IC2") (pin "41") (pinfunction "VSS_41") (pintype "bidirectional"))
      (node (ref "IC2") (pin "55") (pinfunction "VSS_55") (pintype "bidirectional"))
      (node (ref "IC2") (pin "72") (pinfunction "VSS_72") (pintype "bidirectional"))
      (node (ref "IC2") (pin "83") (pinfunction "VSS_83") (pintype "bidirectional"))
      (node (ref "IC2") (pin "97") (pinfunction "VSS_97") (pintype "bidirectional"))
      (node (ref "IC3") (pin "1") (pinfunction "GND_1") (pintype "bidirectional"))
      (node (ref "IC4") (pin "3") (pinfunction "VDD_3") (pintype "bidirectional"))
      (node (ref "IC5") (pin "10") (pinfunction "PGND2_10") (pintype "bidirectional"))
      (node (ref "IC5") (pin "18") (pinfunction "GND_18") (pintype "bidirectional"))
      (node (ref "IC5") (pin "3") (pinfunction "PGND_3") (pintype "bidirectional"))
      (node (ref "IC5") (pin "4") (pinfunction "PGND_4") (pintype "bidirectional"))
      (node (ref "IC5") (pin "9") (pinfunction "PGND2_9") (pintype "bidirectional"))
      (node (ref "IC6") (pin "10") (pinfunction "PGND2_10") (pintype "bidirectional"))
      (node (ref "IC6") (pin "18") (pinfunction "GND_18") (pintype "bidirectional"))
      (node (ref "IC6") (pin "3") (pinfunction "PGND_3") (pintype "bidirectional"))
      (node (ref "IC6") (pin "4") (pinfunction "PGND_4") (pintype "bidirectional"))
      (node (ref "IC6") (pin "9") (pinfunction "PGND2_9") (pintype "bidirectional"))
      (node (ref "IC7") (pin "15") (pinfunction "GND_15") (pintype "bidirectional"))
      (node (ref "IR") (pin "3") (pinfunction "GND_3") (pintype "bidirectional"))
      (node (ref "J2") (pin "10") (pinfunction "10_10") (pintype "bidirectional"))
      (node (ref "J2") (pin "11") (pinfunction "11_11") (pintype "bidirectional"))
      (node (ref "J2") (pin "12") (pinfunction "12_12") (pintype "bidirectional"))
      (node (ref "J2") (pin "13") (pinfunction "13_13") (pintype "bidirectional"))
      (node (ref "J2") (pin "14") (pinfunction "14_14") (pintype "bidirectional"))
      (node (ref "J2") (pin "15") (pinfunction "15_15") (pintype "bidirectional"))
      (node (ref "J2") (pin "9") (pinfunction "9_9") (pintype "bidirectional"))
      (node (ref "J3") (pin "5") (pinfunction "GND_5") (pintype "bidirectional"))
      (node (ref "J4") (pin "3") (pinfunction "3_3") (pintype "bidirectional"))
      (node (ref "J4") (pin "5") (pinfunction "5_5") (pintype "bidirectional"))
      (node (ref "J4") (pin "6") (pinfunction "6_6") (pintype "bidirectional"))
      (node (ref "J4") (pin "G1") (pinfunction "10_G1") (pintype "bidirectional"))
      (node (ref "J4") (pin "G2") (pinfunction "11_G2") (pintype "bidirectional"))
      (node (ref "J5") (pin "10") (pinfunction "10_10") (pintype "bidirectional"))
      (node (ref "J5") (pin "11") (pinfunction "11_11") (pintype "bidirectional"))
      (node (ref "J5") (pin "12") (pinfunction "12_12") (pintype "bidirectional"))
      (node (ref "J5") (pin "13") (pinfunction "13_13") (pintype "bidirectional"))
      (node (ref "J5") (pin "14") (pinfunction "14_14") (pintype "bidirectional"))
      (node (ref "J5") (pin "15") (pinfunction "15_15") (pintype "bidirectional"))
      (node (ref "J5") (pin "9") (pinfunction "9_9") (pintype "bidirectional"))
      (node (ref "J6") (pin "5") (pinfunction "5_5") (pintype "bidirectional"))
      (node (ref "J6") (pin "7") (pinfunction "7_7") (pintype "bidirectional"))
      (node (ref "J7") (pin "4") (pinfunction "4_4") (pintype "bidirectional"))
      (node (ref "J8") (pin "16") (pinfunction "16_16") (pintype "bidirectional"))
      (node (ref "SW1") (pin "1") (pinfunction "1_1") (pintype "bidirectional"))
    )
    (net (code "70") (name "Net-(CN1-P$2)") (class "Default")
      (node (ref "CN1") (pin "2") (pinfunction "P$2_2") (pintype "bidirectional"))
      (node (ref "IC2") (pin "6") (pinfunction "P0.26/AD0.3/AOUT/RXD3_6") (pintype "bidirectional"))
    )
    (net (code "71") (name "Net-(CN1-P$3)") (class "Default")
      (node (ref "CN1") (pin "3") (pinfunction "P$3_3") (pintype "bidirectional"))
      (node (ref "IC2") (pin "7") (pinfunction "P0.25/AD0.2/I2SRX_SDA/TXD3_7") (pintype "bidirectional"))
    )
    (net (code "72") (name "Net-(D1-Pad+)") (class "Default")
      (node (ref "D1") (pin "+") (pinfunction "+_+") (pintype "passive"))
      (node (ref "R2") (pin "2") (pinfunction "2_2") (pintype "passive"))
    )
    (net (code "73") (name "Net-(D2-Pad+)") (class "Default")
      (node (ref "D2") (pin "+") (pinfunction "+_+") (pintype "passive"))
      (node (ref "R3") (pin "2") (pinfunction "2_2") (pintype "passive"))
    )
    (net (code "74") (name "Net-(D3-Pad+)") (class "Default")
      (node (ref "D3") (pin "+") (pinfunction "+_+") (pintype "passive"))
      (node (ref "R4") (pin "2") (pinfunction "2_2") (pintype "passive"))
    )
    (net (code "75") (name "Net-(IC2-P0.2{slash}TXD0{slash}AD0.7)") (class "Default")
      (node (ref "IC2") (pin "98") (pinfunction "P0.2/TXD0/AD0.7_98") (pintype "bidirectional"))
      (node (ref "IC7") (pin "11") (pinfunction "DIN1_11") (pintype "input"))
    )
    (net (code "76") (name "Net-(IC2-P0.3{slash}RXD0{slash}AD0.6)") (class "Default")
      (node (ref "IC2") (pin "99") (pinfunction "P0.3/RXD0/AD0.6_99") (pintype "bidirectional"))
      (node (ref "IC7") (pin "12") (pinfunction "ROUT1_12") (pintype "bidirectional"))
    )
    (net (code "77") (name "Net-(IC2-P0.10{slash}TXD2{slash}SDA2{slash}MAT3.0)") (class "Default")
      (node (ref "IC2") (pin "48") (pinfunction "P0.10/TXD2/SDA2/MAT3.0_48") (pintype "bidirectional"))
      (node (ref "J1") (pin "1") (pinfunction "1_1") (pintype "bidirectional"))
      (node (ref "J2") (pin "1") (pinfunction "1_1") (pintype "bidirectional"))
      (node (ref "J2") (pin "16") (pinfunction "16_16") (pintype "bidirectional"))
    )
    (net (code "78") (name "Net-(IC2-P0.18{slash}DCD1{slash}MOSI0{slash}MOSI1)") (class "Default")
      (node (ref "IC2") (pin "60") (pinfunction "P0.18/DCD1/MOSI0/MOSI1_60") (pintype "bidirectional"))
      (node (ref "R10") (pin "1") (pinfunction "1_1") (pintype "passive"))
    )
    (net (code "79") (name "Net-(IC2-P0.29{slash}USB_D+)") (class "Default")
      (node (ref "C4") (pin "2") (pinfunction "2_2") (pintype "passive"))
      (node (ref "IC2") (pin "29") (pinfunction "P0.29/USB_D+_29") (pintype "bidirectional"))
      (node (ref "R7") (pin "1") (pinfunction "1_1") (pintype "passive"))
    )
    (net (code "80") (name "Net-(IC2-P0.30{slash}USB_D-)") (class "Default")
      (node (ref "C5") (pin "2") (pinfunction "2_2") (pintype "passive"))
      (node (ref "IC2") (pin "30") (pinfunction "P0.30/USB_D-_30") (pintype "bidirectional"))
      (node (ref "R6") (pin "1") (pinfunction "1_1") (pintype "passive"))
    )
    (net (code "81") (name "Net-(IC2-P1.30{slash}VBUS{slash}AD0.4)") (class "Default")
      (node (ref "IC2") (pin "21") (pinfunction "P1.30/VBUS/AD0.4_21") (pintype "bidirectional"))
      (node (ref "R14") (pin "2") (pinfunction "2_2") (pintype "passive"))
    )
    (net (code "82") (name "Net-(IC2-P2.10{slash}EINT0N{slash}NMI)") (class "Default")
      (node (ref "IC2") (pin "53") (pinfunction "P2.10/EINT0N/NMI_53") (pintype "bidirectional"))
      (node (ref "R12") (pin "1") (pinfunction "1_1") (pintype "passive"))
      (node (ref "SW1") (pin "2") (pinfunction "2_2") (pintype "bidirectional"))
    )
    (net (code "83") (name "Net-(IC2-P4.28{slash}RX_MCLK{slash}MAT2.0{slash}TXD3)") (class "Default")
      (node (ref "IC2") (pin "82") (pinfunction "P4.28/RX_MCLK/MAT2.0/TXD3_82") (pintype "bidirectional"))
      (node (ref "J7") (pin "1") (pinfunction "1_1") (pintype "bidirectional"))
    )
    (net (code "84") (name "Net-(IC2-P4.29{slash}TX_MCLK{slash}MAT2.1{slash}RXD3)") (class "Default")
      (node (ref "IC2") (pin "85") (pinfunction "P4.29/TX_MCLK/MAT2.1/RXD3_85") (pintype "bidirectional"))
      (node (ref "J7") (pin "5") (pinfunction "5_5") (pintype "bidirectional"))
    )
    (net (code "85") (name "Net-(IC2-X1)") (class "Default")
      (node (ref "C14") (pin "2") (pinfunction "2_2") (pintype "passive"))
      (node (ref "IC2") (pin "22") (pinfunction "X1_22") (pintype "bidirectional"))
      (node (ref "Y1") (pin "1") (pinfunction "1_1") (pintype "passive"))
    )
    (net (code "86") (name "Net-(IC2-X2)") (class "Default")
      (node (ref "C13") (pin "2") (pinfunction "2_2") (pintype "passive"))
      (node (ref "IC2") (pin "23") (pinfunction "X2_23") (pintype "bidirectional"))
      (node (ref "Y1") (pin "2") (pinfunction "2_2") (pintype "passive"))
    )
    (net (code "87") (name "Net-(IC7-C1+)") (class "Default")
      (node (ref "C32") (pin "1") (pinfunction "1_1") (pintype "passive"))
      (node (ref "IC7") (pin "1") (pinfunction "C1+_1") (pintype "bidirectional"))
    )
    (net (code "88") (name "Net-(IC7-C1-)") (class "Default")
      (node (ref "C32") (pin "2") (pinfunction "2_2") (pintype "passive"))
      (node (ref "IC7") (pin "3") (pinfunction "C1-_3") (pintype "bidirectional"))
    )
    (net (code "89") (name "Net-(IC7-C2+)") (class "Default")
      (node (ref "C30") (pin "2") (pinfunction "2_2") (pintype "passive"))
      (node (ref "IC7") (pin "4") (pinfunction "C2+_4") (pintype "bidirectional"))
    )
    (net (code "90") (name "Net-(IC7-C2-)") (class "Default")
      (node (ref "C30") (pin "1") (pinfunction "1_1") (pintype "passive"))
      (node (ref "IC7") (pin "5") (pinfunction "C2-_5") (pintype "bidirectional"))
    )
    (net (code "91") (name "Net-(IC7-V+)") (class "Default")
      (node (ref "C31") (pin "1") (pinfunction "1_1") (pintype "passive"))
      (node (ref "IC7") (pin "2") (pinfunction "V+_2") (pintype "bidirectional"))
    )
    (net (code "92") (name "Net-(IC7-V-)") (class "Default")
      (node (ref "C29") (pin "2") (pinfunction "2_2") (pintype "passive"))
      (node (ref "IC7") (pin "6") (pinfunction "V-_6") (pintype "bidirectional"))
    )
    (net (code "93") (name "Net-(J3-DM)") (class "Default")
      (node (ref "J3") (pin "2") (pinfunction "DM_2") (pintype "bidirectional"))
      (node (ref "R6") (pin "2") (pinfunction "2_2") (pintype "passive"))
    )
    (net (code "94") (name "Net-(J3-DP)") (class "Default")
      (node (ref "J3") (pin "3") (pinfunction "DP_3") (pintype "bidirectional"))
      (node (ref "R7") (pin "2") (pinfunction "2_2") (pintype "passive"))
      (node (ref "R8") (pin "1") (pinfunction "1_1") (pintype "passive"))
    )
    (net (code "95") (name "Net-(Q1-B)") (class "Default")
      (node (ref "Q1") (pin "1") (pinfunction "B_1") (pintype "passive"))
      (node (ref "R5") (pin "2") (pinfunction "2_2") (pintype "passive"))
    )
    (net (code "96") (name "Net-(Q1-C)") (class "Default")
      (node (ref "Q1") (pin "3") (pinfunction "C_3") (pintype "passive"))
      (node (ref "R8") (pin "2") (pinfunction "2_2") (pintype "passive"))
    )
    (net (code "97") (name "VCC") (class "Default")
      (node (ref "C15") (pin "2") (pinfunction "2_2") (pintype "passive"))
      (node (ref "C33") (pin "2") (pinfunction "2_2") (pintype "passive"))
      (node (ref "C6") (pin "1") (pinfunction "1_1") (pintype "passive"))
      (node (ref "C7") (pin "1") (pinfunction "1_1") (pintype "passive"))
      (node (ref "C8") (pin "1") (pinfunction "1_1") (pintype "passive"))
      (node (ref "IC1") (pin "2") (pinfunction "VSS_2") (pintype "bidirectional"))
      (node (ref "IC3") (pin "3") (pinfunction "IN_3") (pintype "bidirectional"))
      (node (ref "IC4") (pin "2") (pinfunction "VSS_2") (pintype "bidirectional"))
      (node (ref "IC7") (pin "16") (pinfunction "VCC_16") (pintype "bidirectional"))
      (node (ref "J3") (pin "1") (pinfunction "VCC_1") (pintype "bidirectional"))
      (node (ref "R14") (pin "1") (pinfunction "1_1") (pintype "passive"))
    )
    (net (code "98") (name "VDD") (class "Default")
      (node (ref "C1") (pin "2") (pinfunction "2_2") (pintype "passive"))
      (node (ref "C10") (pin "1") (pinfunction "1_1") (pintype "passive"))
      (node (ref "C11") (pin "2") (pinfunction "2_2") (pintype "passive"))
      (node (ref "C12") (pin "2") (pinfunction "2_2") (pintype "passive"))
      (node (ref "C18") (pin "2") (pinfunction "2_2") (pintype "passive"))
      (node (ref "C19") (pin "2") (pinfunction "2_2") (pintype "passive"))
      (node (ref "C2") (pin "2") (pinfunction "2_2") (pintype "passive"))
      (node (ref "C20") (pin "2") (pinfunction "2_2") (pintype "passive"))
      (node (ref "C21") (pin "2") (pinfunction "2_2") (pintype "passive"))
      (node (ref "C22") (pin "2") (pinfunction "2_2") (pintype "passive"))
      (node (ref "C25") (pin "1") (pinfunction "1_1") (pintype "passive"))
      (node (ref "C26") (pin "1") (pinfunction "1_1") (pintype "passive"))
      (node (ref "C27") (pin "2") (pinfunction "2_2") (pintype "passive"))
      (node (ref "C28") (pin "2") (pinfunction "2_2") (pintype "passive"))
      (node (ref "C3") (pin "2") (pinfunction "2_2") (pintype "passive"))
      (node (ref "C9") (pin "1") (pinfunction "1_1") (pintype "passive"))
      (node (ref "IC2") (pin "10") (pinfunction "VDDA_10") (pintype "bidirectional"))
      (node (ref "IC2") (pin "12") (pinfunction "VREFP_12") (pintype "bidirectional"))
      (node (ref "IC2") (pin "19") (pinfunction "VBAT_19") (pintype "bidirectional"))
      (node (ref "IC2") (pin "28") (pinfunction "VDD3.3V_28") (pintype "bidirectional"))
      (node (ref "IC2") (pin "42") (pinfunction "VDDREG3.3V_42") (pintype "bidirectional"))
      (node (ref "IC2") (pin "54") (pinfunction "VDD3.3V_54") (pintype "bidirectional"))
      (node (ref "IC2") (pin "71") (pinfunction "VDD3.3V_71") (pintype "bidirectional"))
      (node (ref "IC2") (pin "84") (pinfunction "VDDREG3.3V_84") (pintype "bidirectional"))
      (node (ref "IC2") (pin "96") (pinfunction "VDD3.3V_96") (pintype "bidirectional"))
      (node (ref "IC3") (pin "2") (pinfunction "OUT_2") (pintype "bidirectional"))
      (node (ref "IC3") (pin "TER") (pinfunction "OUT_TER") (pintype "bidirectional"))
      (node (ref "IC5") (pin "20") (pinfunction "VCC_20") (pintype "bidirectional"))
      (node (ref "IC6") (pin "20") (pinfunction "VCC_20") (pintype "bidirectional"))
      (node (ref "IR") (pin "2") (pinfunction "VS_2") (pintype "bidirectional"))
      (node (ref "J5") (pin "1") (pinfunction "1_1") (pintype "bidirectional"))
      (node (ref "J5") (pin "16") (pinfunction "16_16") (pintype "bidirectional"))
      (node (ref "J7") (pin "6") (pinfunction "6_6") (pintype "bidirectional"))
      (node (ref "J7") (pin "8") (pinfunction "8_8") (pintype "bidirectional"))
      (node (ref "Q1") (pin "2") (pinfunction "E_2") (pintype "passive"))
      (node (ref "R1") (pin "2") (pinfunction "2_2") (pintype "passive"))
      (node (ref "R12") (pin "2") (pinfunction "2_2") (pintype "passive"))
    )
    (net (code "99") (name "unconnected-(IC2-NC-Pad13)") (class "Default")
      (node (ref "IC2") (pin "13") (pinfunction "NC_13") (pintype "bidirectional"))
    )
    (net (code "100") (name "unconnected-(IC2-P0.7{slash}I2STX_CLK{slash}SCK1{slash}MAT2.1-Pad78)") (class "Default")
      (node (ref "IC2") (pin "78") (pinfunction "P0.7/I2STX_CLK/SCK1/MAT2.1_78") (pintype "bidirectional"))
    )
    (net (code "101") (name "unconnected-(IC2-P0.19{slash}DSR1{slash}MCICLK{slash}SDA1-Pad59)") (class "Default")
      (node (ref "IC2") (pin "59") (pinfunction "P0.19/DSR1/MCICLK/SDA1_59") (pintype "bidirectional"))
    )
    (net (code "102") (name "unconnected-(IC2-P0.23{slash}AD0.0{slash}I2SRX_CLK{slash}CAP3.0-Pad9)") (class "Default")
      (node (ref "IC2") (pin "9") (pinfunction "P0.23/AD0.0/I2SRX_CLK/CAP3.0_9") (pintype "bidirectional"))
    )
    (net (code "103") (name "unconnected-(IC2-P0.28{slash}SCL0{slash}USB_SCL-Pad24)") (class "Default")
      (node (ref "IC2") (pin "24") (pinfunction "P0.28/SCL0/USB_SCL_24") (pintype "bidirectional"))
    )
    (net (code "104") (name "unconnected-(IC2-P1.15{slash}ENET-RX_CLK-Pad88)") (class "Default")
      (node (ref "IC2") (pin "88") (pinfunction "P1.15/ENET-RX_CLK_88") (pintype "bidirectional"))
    )
    (net (code "105") (name "unconnected-(IC2-P1.16{slash}ENET-MDC-Pad87)") (class "Default")
      (node (ref "IC2") (pin "87") (pinfunction "P1.16/ENET-MDC_87") (pintype "bidirectional"))
    )
    (net (code "106") (name "unconnected-(IC2-P1.17{slash}ENET-MDIO-Pad86)") (class "Default")
      (node (ref "IC2") (pin "86") (pinfunction "P1.17/ENET-MDIO_86") (pintype "bidirectional"))
    )
    (net (code "107") (name "unconnected-(IC2-P1.18{slash}USB_UP{slash}PWM1.1{slash}CAP1.0-Pad32)") (class "Default")
      (node (ref "IC2") (pin "32") (pinfunction "P1.18/USB_UP/PWM1.1/CAP1.0_32") (pintype "bidirectional"))
    )
    (net (code "108") (name "unconnected-(IC2-P1.19{slash}MC0A{slash}USB_PPWR{slash}CAP1.1-Pad33)") (class "Default")
      (node (ref "IC2") (pin "33") (pinfunction "P1.19/MC0A/USB_PPWR/CAP1.1_33") (pintype "bidirectional"))
    )
    (net (code "109") (name "unconnected-(IC2-P1.20{slash}MCFB0{slash}PWM1.2{slash}SCK0-Pad34)") (class "Default")
      (node (ref "IC2") (pin "34") (pinfunction "P1.20/MCFB0/PWM1.2/SCK0_34") (pintype "bidirectional"))
    )
    (net (code "110") (name "unconnected-(IC2-P1.22{slash}MC0B{slash}USB_PWRD{slash}MAT1.0-Pad36)") (class "Default")
      (node (ref "IC2") (pin "36") (pinfunction "P1.22/MC0B/USB_PWRD/MAT1.0_36") (pintype "bidirectional"))
    )
    (net (code "111") (name "unconnected-(IC2-P1.24{slash}MCFB2{slash}PWM1.5{slash}MOSI0-Pad38)") (class "Default")
      (node (ref "IC2") (pin "38") (pinfunction "P1.24/MCFB2/PWM1.5/MOSI0_38") (pintype "bidirectional"))
    )
    (net (code "112") (name "unconnected-(IC2-P1.25{slash}MC1A{slash}MAT1.1-Pad39)") (class "Default")
      (node (ref "IC2") (pin "39") (pinfunction "P1.25/MC1A/MAT1.1_39") (pintype "bidirectional"))
    )
    (net (code "113") (name "unconnected-(IC2-P1.28{slash}MC2A{slash}PCAP1.0{slash}MAT0.0-Pad44)") (class "Default")
      (node (ref "IC2") (pin "44") (pinfunction "P1.28/MC2A/PCAP1.0/MAT0.0_44") (pintype "bidirectional"))
    )
    (net (code "114") (name "unconnected-(IC2-P1.29{slash}MC2B{slash}PCAP1.1{slash}MAT0.1-Pad45)") (class "Default")
      (node (ref "IC2") (pin "45") (pinfunction "P1.29/MC2B/PCAP1.1/MAT0.1_45") (pintype "bidirectional"))
    )
    (net (code "115") (name "unconnected-(IC2-P1.31{slash}SCK1{slash}AD0.5-Pad20)") (class "Default")
      (node (ref "IC2") (pin "20") (pinfunction "P1.31/SCK1/AD0.5_20") (pintype "bidirectional"))
    )
    (net (code "116") (name "unconnected-(IC2-P2.2{slash}PWM1.3{slash}CTS1{slash}TRACEDATA3-Pad73)") (class "Default")
      (node (ref "IC2") (pin "73") (pinfunction "P2.2/PWM1.3/CTS1/TRACEDATA3_73") (pintype "bidirectional"))
    )
    (net (code "117") (name "unconnected-(IC2-P2.11{slash}EINT1N{slash}I2STX_CLK-Pad52)") (class "Default")
      (node (ref "IC2") (pin "52") (pinfunction "P2.11/EINT1N/I2STX_CLK_52") (pintype "bidirectional"))
    )
    (net (code "118") (name "unconnected-(IC2-P2.12{slash}EINT2N{slash}I2STX_WS-Pad51)") (class "Default")
      (node (ref "IC2") (pin "51") (pinfunction "P2.12/EINT2N/I2STX_WS_51") (pintype "bidirectional"))
    )
    (net (code "119") (name "unconnected-(IC2-P2.13{slash}EINT3N{slash}I2STX_SDA-Pad50)") (class "Default")
      (node (ref "IC2") (pin "50") (pinfunction "P2.13/EINT3N/I2STX_SDA_50") (pintype "bidirectional"))
    )
    (net (code "120") (name "unconnected-(IC2-RSTOUTN-Pad14)") (class "Default")
      (node (ref "IC2") (pin "14") (pinfunction "RSTOUTN_14") (pintype "bidirectional"))
    )
    (net (code "121") (name "unconnected-(IC2-RTCX1-Pad16)") (class "Default")
      (node (ref "IC2") (pin "16") (pinfunction "RTCX1_16") (pintype "bidirectional"))
    )
    (net (code "122") (name "unconnected-(IC2-RTCX2-Pad18)") (class "Default")
      (node (ref "IC2") (pin "18") (pinfunction "RTCX2_18") (pintype "bidirectional"))
    )
    (net (code "123") (name "unconnected-(J3-GND-Pad6)") (class "Default")
      (node (ref "J3") (pin "6") (pinfunction "GND_6") (pintype "bidirectional"))
    )
    (net (code "124") (name "unconnected-(J3-GND-Pad7)") (class "Default")
      (node (ref "J3") (pin "7") (pinfunction "GND_7") (pintype "bidirectional"))
    )
    (net (code "125") (name "unconnected-(J3-ID-Pad4)") (class "Default")
      (node (ref "J3") (pin "4") (pinfunction "ID_4") (pintype "bidirectional"))
    )
    (net (code "126") (name "unconnected-(J4-Pad4)") (class "Default")
      (node (ref "J4") (pin "4") (pinfunction "4_4") (pintype "bidirectional"))
    )
    (net (code "127") (name "unconnected-(J4-Pad9)") (class "Default")
      (node (ref "J4") (pin "9") (pinfunction "9_9") (pintype "bidirectional"))
    )
    (net (code "128") (name "unconnected-(J6-10-PadG1)") (class "Default")
      (node (ref "J6") (pin "G1") (pinfunction "10_G1") (pintype "bidirectional"))
    )
    (net (code "129") (name "unconnected-(J6-11-PadG2)") (class "Default")
      (node (ref "J6") (pin "G2") (pinfunction "11_G2") (pintype "bidirectional"))
    )
    (net (code "130") (name "unconnected-(J6-Pad4)") (class "Default")
      (node (ref "J6") (pin "4") (pinfunction "4_4") (pintype "bidirectional"))
    )
    (net (code "131") (name "unconnected-(J6-Pad8)") (class "Default")
      (node (ref "J6") (pin "8") (pinfunction "8_8") (pintype "bidirectional"))
    )
    (net (code "132") (name "unconnected-(J6-Pad9)") (class "Default")
      (node (ref "J6") (pin "9") (pinfunction "9_9") (pintype "bidirectional"))
    )
  )
)
